# 50_Gesti_n_Alimentaci_n.net
KiCad netlist of a schematic drawn in Altium Designer
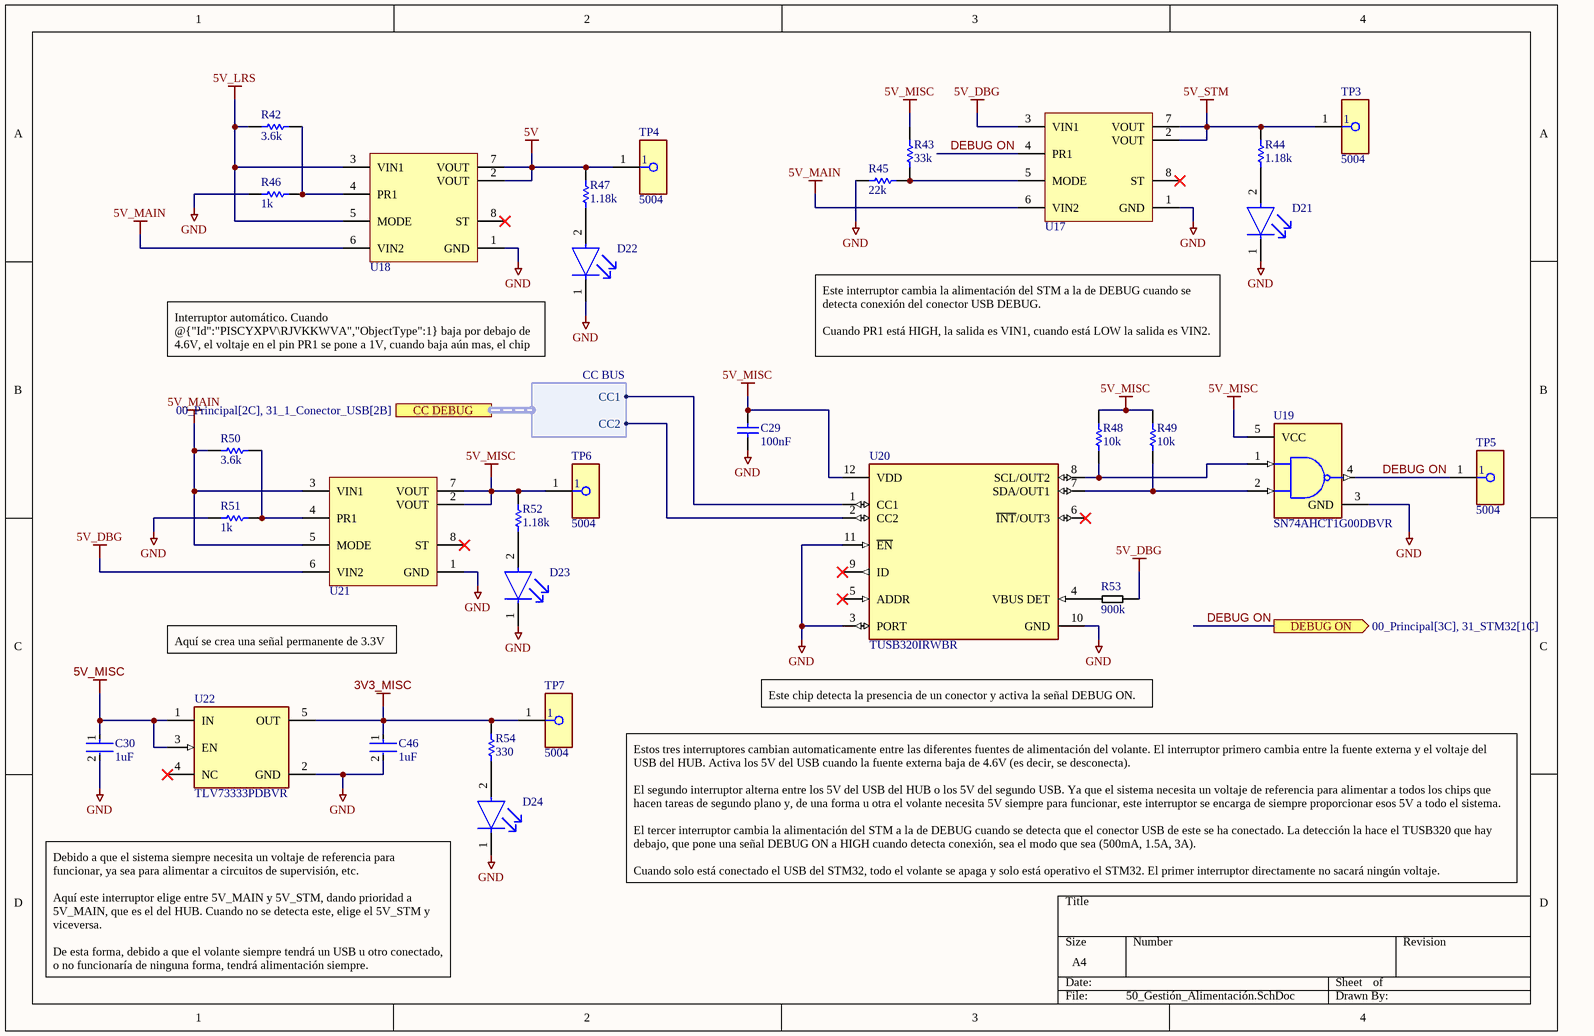
[diagram p0: 50_Gestión_Alimentación.SchDoc]

(export (version "E")
  (design (tool "Eeschema 10.0.6"))
  (components
    (comp (ref "C29")
      (value "100nF")
      (footprint "CAPC1005X55X25NL05T05")
      (fields (field (name "MANUFACTURER") "Vitramon") (field (name "PART NUMBER") "VJ0402Y104KXJCW1BC"))
      (libsource (lib "Altium Content Vault") (part "CAP"))
    )
    (comp (ref "C30")
      (value "1uF")
      (footprint "FP-C0402C-BB-IPC_B")
      (description "CAP CER 1UF 16V X5R 0402")
      (fields (field (name "TOLERANCE") "10%"))
      (libsource (lib "Altium Content Vault") (part "b4654b650e69147ec39a6b967a45e02"))
    )
    (comp (ref "C46")
      (value "1uF")
      (footprint "FP-C0402C-BB-IPC_B")
      (description "CAP CER 1UF 16V X5R 0402")
      (fields (field (name "TOLERANCE") "10%"))
      (libsource (lib "Altium Content Vault") (part "b4654b650e69147ec39a6b967a45e02"))
    )
    (comp (ref "D21")
      (value "APHD1608LZGCK")
      (footprint "FP-APHD1608LZGCK-MFG")
      (description "LED GREEN CLEAR 1608 SMD")
      (libsource (lib "Altium Content Vault") (part "8706943c75ba83719d021d2fdc84c58"))
    )
    (comp (ref "D22")
      (value "APHD1608LZGCK")
      (footprint "FP-APHD1608LZGCK-MFG")
      (description "LED GREEN CLEAR 1608 SMD")
      (libsource (lib "Altium Content Vault") (part "8706943c75ba83719d021d2fdc84c58"))
    )
    (comp (ref "D23")
      (value "APHD1608LZGCK")
      (footprint "FP-APHD1608LZGCK-MFG")
      (description "LED GREEN CLEAR 1608 SMD")
      (libsource (lib "Altium Content Vault") (part "8706943c75ba83719d021d2fdc84c58"))
    )
    (comp (ref "D24")
      (value "APHD1608LZGCK")
      (footprint "FP-APHD1608LZGCK-MFG")
      (description "LED GREEN CLEAR 1608 SMD")
      (libsource (lib "Altium Content Vault") (part "8706943c75ba83719d021d2fdc84c58"))
    )
    (comp (ref "R42")
      (value "3.6k")
      (footprint "RESC1005X40X25ML10T10")
      (fields (field (name "MANUFACTURER") "Panasonic") (field (name "PART NUMBER") "ERA-2AEB362X"))
      (libsource (lib "Altium Content Vault") (part "RES"))
    )
    (comp (ref "R43")
      (value "33k")
      (footprint "RESC1005X40X25NL10T10")
      (fields (field (name "PART NUMBER") "ERA-2AED333X") (field (name "MANUFACTURER") "Panasonic"))
      (libsource (lib "Altium Content Vault") (part "RES"))
    )
    (comp (ref "R44")
      (value "1.18k")
      (footprint "RESC1005X40X25NL05T05")
      (fields (field (name "PART NUMBER") "ERJ-2RKF1181X") (field (name "MANUFACTURER") "Panasonic"))
      (libsource (lib "Altium Content Vault") (part "RES"))
    )
    (comp (ref "R45")
      (value "22k")
      (footprint "RESC1005X40X25NL10T10")
      (fields (field (name "MANUFACTURER") "Panasonic") (field (name "PART NUMBER") "ERA-2AED223X"))
      (libsource (lib "Altium Content Vault") (part "RES"))
    )
    (comp (ref "R46")
      (value "1k")
      (footprint "RESC1005X40X25NL05T05")
      (description "Chip Resistor, 1 KOhm, +/- 1%, 100 mW, -55 to 155 degC, 0402 (1005 Metric), RoHS, Tape and Reel")
      (fields (field (name "PARTNUMBER") "ERJ-2RKF1001X") (field (name "MANUFACTURER") "Basic Passives"))
      (libsource (lib "Altium Content Vault") (part "RES-2"))
    )
    (comp (ref "R47")
      (value "1.18k")
      (footprint "RESC1005X40X25NL05T05")
      (fields (field (name "PART NUMBER") "ERJ-2RKF1181X") (field (name "MANUFACTURER") "Panasonic"))
      (libsource (lib "Altium Content Vault") (part "RES"))
    )
    (comp (ref "R48")
      (value "10k")
      (footprint "RESC1005X40X25ML05T05")
      (fields (field (name "MANUFACTURER") "Panasonic") (field (name "PART NUMBER") "ERJ-2RHD1002X"))
      (libsource (lib "Altium Content Vault") (part "RES"))
    )
    (comp (ref "R49")
      (value "10k")
      (footprint "RESC1005X40X25ML05T05")
      (fields (field (name "MANUFACTURER") "Panasonic") (field (name "PART NUMBER") "ERJ-2RHD1002X"))
      (libsource (lib "Altium Content Vault") (part "RES"))
    )
    (comp (ref "R50")
      (value "3.6k")
      (footprint "RESC1005X40X25ML10T10")
      (fields (field (name "MANUFACTURER") "Panasonic") (field (name "PART NUMBER") "ERA-2AEB362X"))
      (libsource (lib "Altium Content Vault") (part "RES"))
    )
    (comp (ref "R51")
      (value "1k")
      (footprint "RESC1005X40X25NL05T05")
      (description "Chip Resistor, 1 KOhm, +/- 1%, 100 mW, -55 to 155 degC, 0402 (1005 Metric), RoHS, Tape and Reel")
      (fields (field (name "PARTNUMBER") "ERJ-2RKF1001X") (field (name "MANUFACTURER") "Basic Passives"))
      (libsource (lib "Altium Content Vault") (part "RES-2"))
    )
    (comp (ref "R52")
      (value "1.18k")
      (footprint "RESC1005X40X25NL05T05")
      (fields (field (name "PART NUMBER") "ERJ-2RKF1181X") (field (name "MANUFACTURER") "Panasonic"))
      (libsource (lib "Altium Content Vault") (part "RES"))
    )
    (comp (ref "R53")
      (value "900k")
      (footprint "RES 1206")
      (description "900k Resistor 200V 1206 0.5%")
      (libsource (lib "Esquemas") (part "RT1206CRE07900KL"))
    )
    (comp (ref "R54")
      (value "330")
      (footprint "RESC1005X40X25NL10T10")
      (fields (field (name "MANUFACTURER") "Panasonic") (field (name "PART NUMBER") "ERA2AEB331X"))
      (libsource (lib "Altium Content Vault") (part "RES"))
    )
    (comp (ref "TP3")
      (value "5004")
      (footprint "FP-5004-MFG")
      (description "PC TEST POINT MINIATURE YELLOW")
      (fields
        (field (name "MANUFACTURER") "Keystone")
        (field (name "OCTOPART") "https://octopart.com/5004-keystone-28591")
      )
      (libsource (lib "Altium Content Vault") (part "98815daf2f2c152b0c43f5ab9800df6"))
    )
    (comp (ref "TP4")
      (value "5004")
      (footprint "FP-5004-MFG")
      (description "PC TEST POINT MINIATURE YELLOW")
      (fields
        (field (name "MANUFACTURER") "Keystone")
        (field (name "OCTOPART") "https://octopart.com/5004-keystone-28591")
      )
      (libsource (lib "Altium Content Vault") (part "98815daf2f2c152b0c43f5ab9800df6"))
    )
    (comp (ref "TP5")
      (value "5004")
      (footprint "FP-5004-MFG")
      (description "PC TEST POINT MINIATURE YELLOW")
      (fields
        (field (name "MANUFACTURER") "Keystone")
        (field (name "OCTOPART") "https://octopart.com/5004-keystone-28591")
      )
      (libsource (lib "Altium Content Vault") (part "98815daf2f2c152b0c43f5ab9800df6"))
    )
    (comp (ref "TP6")
      (value "5004")
      (footprint "FP-5004-MFG")
      (description "PC TEST POINT MINIATURE YELLOW")
      (fields
        (field (name "MANUFACTURER") "Keystone")
        (field (name "OCTOPART") "https://octopart.com/5004-keystone-28591")
      )
      (libsource (lib "Altium Content Vault") (part "98815daf2f2c152b0c43f5ab9800df6"))
    )
    (comp (ref "TP7")
      (value "5004")
      (footprint "FP-5004-MFG")
      (description "PC TEST POINT MINIATURE YELLOW")
      (fields
        (field (name "MANUFACTURER") "Keystone")
        (field (name "OCTOPART") "https://octopart.com/5004-keystone-28591")
      )
      (libsource (lib "Altium Content Vault") (part "98815daf2f2c152b0c43f5ab9800df6"))
    )
    (comp (ref "U17")
      (value "TPS2117DRLR")
      (footprint "TPS2117DRLR")
      (description "Power Switch ICs - Power Distribution 1.6-V to 5.5-V 20-m ? 4-A low IQ power")
      (libsource (lib "Esquemas") (part "TPS2117DRLR"))
    )
    (comp (ref "U18")
      (value "TPS2117DRLR")
      (footprint "TPS2117DRLR")
      (description "Power Switch ICs - Power Distribution 1.6-V to 5.5-V 20-m ? 4-A low IQ power")
      (libsource (lib "Esquemas") (part "TPS2117DRLR"))
    )
    (comp (ref "U19")
      (value "SN74AHCT1G00DBVR")
      (footprint "FP-DBV0005A-IPC_A")
      (description "IC GATE NAND 1CH 2-INP SOT23-5")
      (libsource (lib "Altium Content Vault") (part "7348cb10480373169dc7360ee9edf5c"))
    )
    (comp (ref "U20")
      (value "TUSB320IRWBR")
      (footprint "FP-RWB0012A-MFG")
      (description "IC INTERFACE SPECIALIZED 12X2QFN")
      (libsource (lib "Altium Content Vault") (part "76af6d7f95a64df20dc6dc148ef600c"))
    )
    (comp (ref "U21")
      (value "TPS2117DRLR")
      (footprint "TPS2117DRLR")
      (description "Power Switch ICs - Power Distribution 1.6-V to 5.5-V 20-m ? 4-A low IQ power")
      (libsource (lib "Esquemas") (part "TPS2117DRLR"))
    )
    (comp (ref "U22")
      (value "TLV73333PDBVR")
      (footprint "FP-DBV0005A-MFG")
      (description "IC REG LINEAR 3.3V 300MA SOT23-5")
      (fields
        (field (name "MANUFACTURER") "Texas Instruments")
        (field (name "OCTOPART") "https://octopart.com/tlv73333pdbvr-texas+instruments-51080890")
      )
      (libsource (lib "Altium Content Vault") (part "10cdd6a861ce8db355dac0efc8b397e"))
    )
  )
  (nets
    (net (code "3") (name "/CC1") (class "Default")
      (node (ref "U20") (pin "1") (pinfunction "CC1_1") (pintype "bidirectional"))
    )
    (net (code "4") (name "/CC2") (class "Default")
      (node (ref "U20") (pin "2") (pinfunction "CC2_2") (pintype "bidirectional"))
    )
    (net (code "5") (name "/DEBUG ON") (class "Default")
      (node (ref "TP5") (pin "1") (pinfunction "1_1") (pintype "passive"))
      (node (ref "U17") (pin "4") (pinfunction "PR1_4") (pintype "passive"))
      (node (ref "U19") (pin "4") (pinfunction "Y_4") (pintype "output"))
    )
    (net (code "7") (name "3V3_MISC") (class "Default")
      (node (ref "C46") (pin "1") (pinfunction "1_1") (pintype "passive"))
      (node (ref "R54") (pin "2") (pinfunction "2_2") (pintype "passive"))
      (node (ref "TP7") (pin "1") (pinfunction "1_1") (pintype "passive"))
      (node (ref "U22") (pin "5") (pinfunction "OUT_5") (pintype "power_in"))
    )
    (net (code "8") (name "5V") (class "Default")
      (node (ref "R47") (pin "2") (pinfunction "2_2") (pintype "passive"))
      (node (ref "TP4") (pin "1") (pinfunction "1_1") (pintype "passive"))
      (node (ref "U18") (pin "2") (pinfunction "VOUT_2") (pintype "passive"))
      (node (ref "U18") (pin "7") (pinfunction "VOUT_7") (pintype "passive"))
    )
    (net (code "9") (name "5V_DBG") (class "Default")
      (node (ref "R53") (pin "1") (pintype "passive"))
      (node (ref "U17") (pin "3") (pinfunction "VIN1_3") (pintype "passive"))
      (node (ref "U21") (pin "6") (pinfunction "VIN2_6") (pintype "passive"))
    )
    (net (code "10") (name "5V_LRS") (class "Default")
      (node (ref "R42") (pin "1") (pinfunction "1_1") (pintype "passive"))
      (node (ref "U18") (pin "3") (pinfunction "VIN1_3") (pintype "passive"))
      (node (ref "U18") (pin "5") (pinfunction "MODE_5") (pintype "passive"))
    )
    (net (code "11") (name "5V_MAIN") (class "Default")
      (node (ref "R50") (pin "1") (pinfunction "1_1") (pintype "passive"))
      (node (ref "U17") (pin "6") (pinfunction "VIN2_6") (pintype "passive"))
      (node (ref "U18") (pin "6") (pinfunction "VIN2_6") (pintype "passive"))
      (node (ref "U21") (pin "3") (pinfunction "VIN1_3") (pintype "passive"))
      (node (ref "U21") (pin "5") (pinfunction "MODE_5") (pintype "passive"))
    )
    (net (code "12") (name "5V_MISC") (class "Default")
      (node (ref "C29") (pin "2") (pinfunction "2_2") (pintype "passive"))
      (node (ref "C30") (pin "1") (pinfunction "1_1") (pintype "passive"))
      (node (ref "R43") (pin "2") (pinfunction "2_2") (pintype "passive"))
      (node (ref "R48") (pin "2") (pinfunction "2_2") (pintype "passive"))
      (node (ref "R49") (pin "2") (pinfunction "2_2") (pintype "passive"))
      (node (ref "R52") (pin "2") (pinfunction "2_2") (pintype "passive"))
      (node (ref "TP6") (pin "1") (pinfunction "1_1") (pintype "passive"))
      (node (ref "U19") (pin "5") (pinfunction "VCC_5") (pintype "power_in"))
      (node (ref "U20") (pin "12") (pinfunction "VDD_12") (pintype "power_in"))
      (node (ref "U21") (pin "2") (pinfunction "VOUT_2") (pintype "passive"))
      (node (ref "U21") (pin "7") (pinfunction "VOUT_7") (pintype "passive"))
      (node (ref "U22") (pin "1") (pinfunction "IN_1") (pintype "power_in"))
      (node (ref "U22") (pin "3") (pinfunction "EN_3") (pintype "input"))
    )
    (net (code "13") (name "5V_STM") (class "Default")
      (node (ref "R44") (pin "2") (pinfunction "2_2") (pintype "passive"))
      (node (ref "TP3") (pin "1") (pinfunction "1_1") (pintype "passive"))
      (node (ref "U17") (pin "2") (pinfunction "VOUT_2") (pintype "passive"))
      (node (ref "U17") (pin "7") (pinfunction "VOUT_7") (pintype "passive"))
    )
    (net (code "14") (name "GND") (class "Default")
      (node (ref "C29") (pin "1") (pinfunction "1_1") (pintype "passive"))
      (node (ref "C30") (pin "2") (pinfunction "2_2") (pintype "passive"))
      (node (ref "C46") (pin "2") (pinfunction "2_2") (pintype "passive"))
      (node (ref "D21") (pin "1") (pinfunction "C_1") (pintype "passive"))
      (node (ref "D22") (pin "1") (pinfunction "C_1") (pintype "passive"))
      (node (ref "D23") (pin "1") (pinfunction "C_1") (pintype "passive"))
      (node (ref "D24") (pin "1") (pinfunction "C_1") (pintype "passive"))
      (node (ref "R45") (pin "1") (pinfunction "1_1") (pintype "passive"))
      (node (ref "R46") (pin "1") (pinfunction "1_1") (pintype "passive"))
      (node (ref "R51") (pin "1") (pinfunction "1_1") (pintype "passive"))
      (node (ref "U17") (pin "1") (pinfunction "GND_1") (pintype "passive"))
      (node (ref "U18") (pin "1") (pinfunction "GND_1") (pintype "passive"))
      (node (ref "U19") (pin "3") (pinfunction "GND_3") (pintype "power_in"))
      (node (ref "U20") (pin "10") (pinfunction "GND_10") (pintype "power_in"))
      (node (ref "U20") (pin "11") (pinfunction "~{EN}_11") (pintype "input"))
      (node (ref "U20") (pin "3") (pinfunction "PORT_3") (pintype "bidirectional"))
      (node (ref "U21") (pin "1") (pinfunction "GND_1") (pintype "passive"))
      (node (ref "U22") (pin "2") (pinfunction "GND_2") (pintype "power_in"))
    )
    (net (code "15") (name "Net-(D21-A)") (class "Default")
      (node (ref "D21") (pin "2") (pinfunction "A_2") (pintype "passive"))
      (node (ref "R44") (pin "1") (pinfunction "1_1") (pintype "passive"))
    )
    (net (code "16") (name "Net-(D22-A)") (class "Default")
      (node (ref "D22") (pin "2") (pinfunction "A_2") (pintype "passive"))
      (node (ref "R47") (pin "1") (pinfunction "1_1") (pintype "passive"))
    )
    (net (code "17") (name "Net-(D23-A)") (class "Default")
      (node (ref "D23") (pin "2") (pinfunction "A_2") (pintype "passive"))
      (node (ref "R52") (pin "1") (pinfunction "1_1") (pintype "passive"))
    )
    (net (code "18") (name "Net-(D24-A)") (class "Default")
      (node (ref "D24") (pin "2") (pinfunction "A_2") (pintype "passive"))
      (node (ref "R54") (pin "1") (pinfunction "1_1") (pintype "passive"))
    )
    (net (code "19") (name "Net-(U17-MODE)") (class "Default")
      (node (ref "R43") (pin "1") (pinfunction "1_1") (pintype "passive"))
      (node (ref "R45") (pin "2") (pinfunction "2_2") (pintype "passive"))
      (node (ref "U17") (pin "5") (pinfunction "MODE_5") (pintype "passive"))
    )
    (net (code "20") (name "Net-(U18-PR1)") (class "Default")
      (node (ref "R42") (pin "2") (pinfunction "2_2") (pintype "passive"))
      (node (ref "R46") (pin "2") (pinfunction "2_2") (pintype "passive"))
      (node (ref "U18") (pin "4") (pinfunction "PR1_4") (pintype "passive"))
    )
    (net (code "21") (name "Net-(U19-A)") (class "Default")
      (node (ref "R48") (pin "1") (pinfunction "1_1") (pintype "passive"))
      (node (ref "U19") (pin "1") (pinfunction "A_1") (pintype "input"))
      (node (ref "U20") (pin "8") (pinfunction "SCL/OUT2_8") (pintype "bidirectional"))
    )
    (net (code "22") (name "Net-(U19-B)") (class "Default")
      (node (ref "R49") (pin "1") (pinfunction "1_1") (pintype "passive"))
      (node (ref "U19") (pin "2") (pinfunction "B_2") (pintype "input"))
      (node (ref "U20") (pin "7") (pinfunction "SDA/OUT1_7") (pintype "bidirectional"))
    )
    (net (code "23") (name "Net-(U20-VBUS_DET)") (class "Default")
      (node (ref "R53") (pin "2") (pintype "passive"))
      (node (ref "U20") (pin "4") (pinfunction "VBUS_DET_4") (pintype "input"))
    )
    (net (code "24") (name "Net-(U21-PR1)") (class "Default")
      (node (ref "R50") (pin "2") (pinfunction "2_2") (pintype "passive"))
      (node (ref "R51") (pin "2") (pinfunction "2_2") (pintype "passive"))
      (node (ref "U21") (pin "4") (pinfunction "PR1_4") (pintype "passive"))
    )
    (net (code "25") (name "unconnected-(U17-ST-Pad8)") (class "Default")
      (node (ref "U17") (pin "8") (pinfunction "ST_8") (pintype "passive+no_connect"))
    )
    (net (code "26") (name "unconnected-(U18-ST-Pad8)") (class "Default")
      (node (ref "U18") (pin "8") (pinfunction "ST_8") (pintype "passive+no_connect"))
    )
    (net (code "27") (name "unconnected-(U20-ADDR-Pad5)") (class "Default")
      (node (ref "U20") (pin "5") (pinfunction "ADDR_5") (pintype "input+no_connect"))
    )
    (net (code "28") (name "unconnected-(U20-ID-Pad9)") (class "Default")
      (node (ref "U20") (pin "9") (pinfunction "ID_9") (pintype "output+no_connect"))
    )
    (net (code "29") (name "unconnected-(U20-~{INT}{slash}OUT3-Pad6)") (class "Default")
      (node (ref "U20") (pin "6") (pinfunction "~{INT}/OUT3_6") (pintype "bidirectional+no_connect"))
    )
    (net (code "30") (name "unconnected-(U21-ST-Pad8)") (class "Default")
      (node (ref "U21") (pin "8") (pinfunction "ST_8") (pintype "passive+no_connect"))
    )
    (net (code "31") (name "unconnected-(U22-NC-Pad4)") (class "Default")
      (node (ref "U22") (pin "4") (pinfunction "NC_4") (pintype "passive+no_connect"))
    )
  )
)
